# IRremote.net
KiCad netlist of a schematic drawn in EAGLE
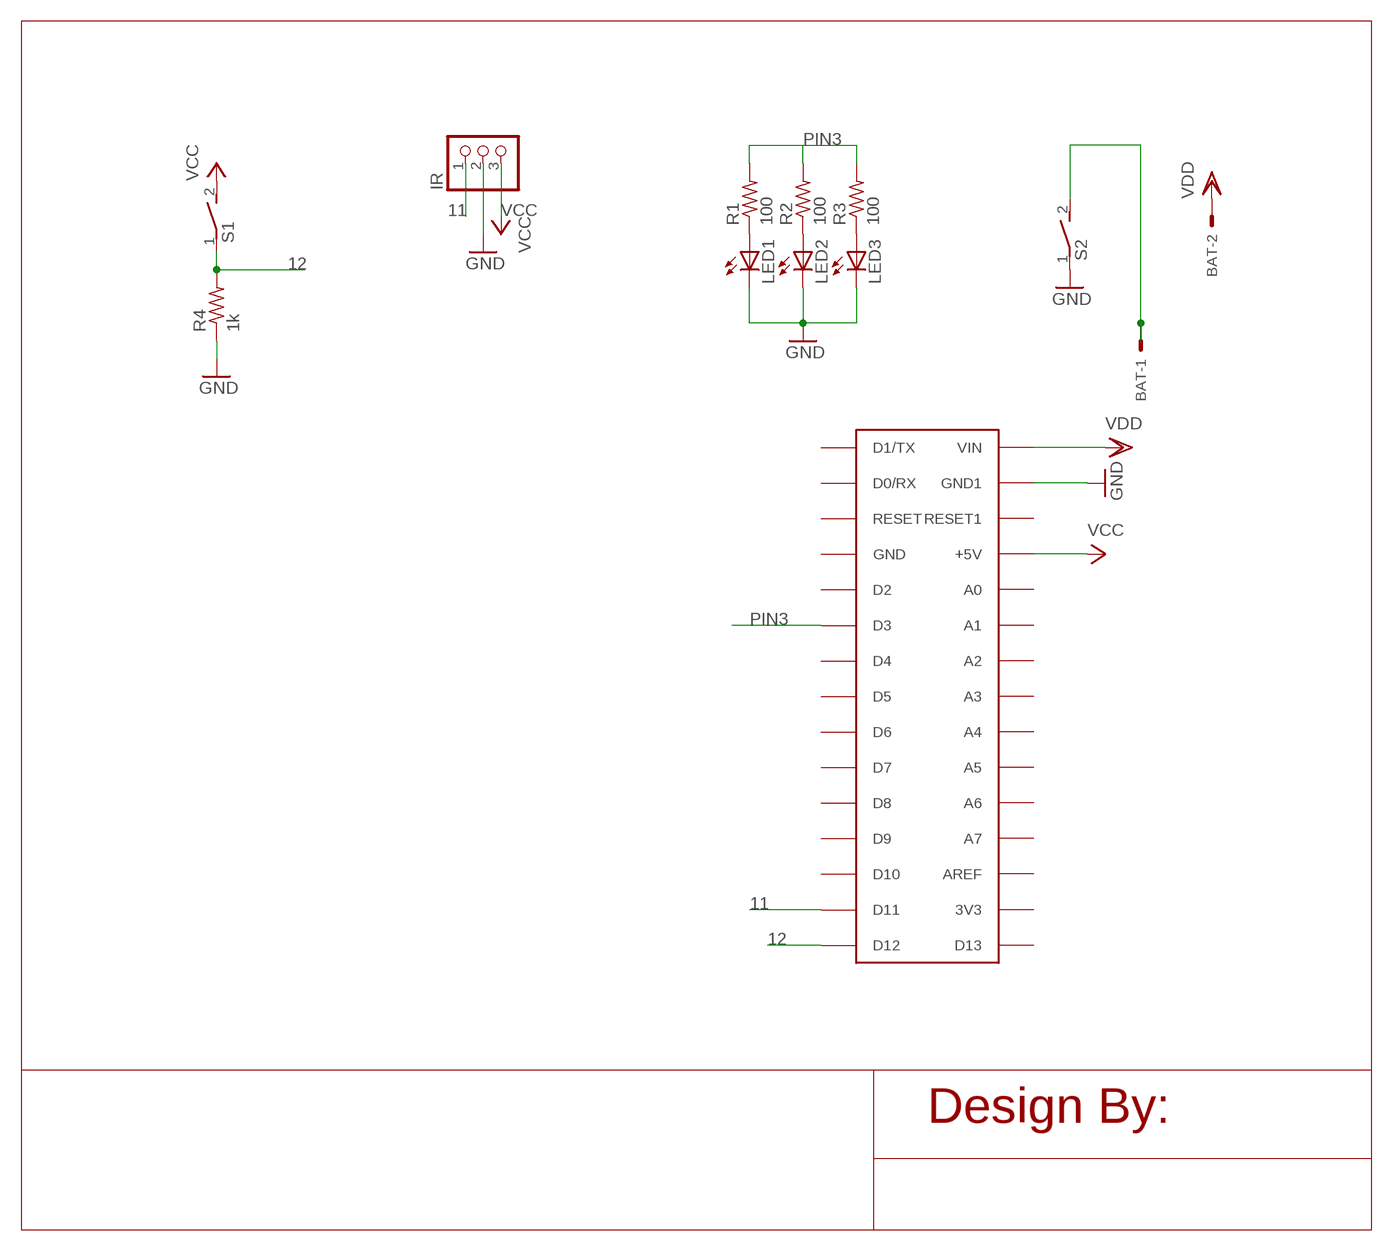
[diagram p0: schematic, sheet 1]

(export (version "E")
  (design (tool "Eeschema 10.0.6"))
  (components
    (comp (ref "ARDIUNO-NANO")
      (value "ARDUINONANO")
      (footprint "eagle-import:PDIP-32")
      (libsource (lib "eagle-import") (part "ARDUINONANO"))
    )
    (comp (ref "BAT")
      (value "22-23-2021")
      (footprint "eagle-import:22-23-2021")
      (fields (field (name "MF") "MOLEX"))
      (libsource (lib "eagle-import") (part "22-23-2021"))
    )
    (comp (ref "IR")
      (value "PINHD-1X3")
      (footprint "eagle-import:1X03")
      (libsource (lib "eagle-import") (part "PINHD-1X3"))
    )
    (comp (ref "LED1")
      (value "LED5MM")
      (footprint "eagle-import:LED5MM")
      (libsource (lib "eagle-import") (part "LED5MM"))
    )
    (comp (ref "LED2")
      (value "LED5MM")
      (footprint "eagle-import:LED5MM")
      (libsource (lib "eagle-import") (part "LED5MM"))
    )
    (comp (ref "LED3")
      (value "LED5MM")
      (footprint "eagle-import:LED5MM")
      (libsource (lib "eagle-import") (part "LED5MM"))
    )
    (comp (ref "R1")
      (value "100")
      (footprint "eagle-import:R0603")
      (libsource (lib "eagle-import") (part "R-US_R0603"))
    )
    (comp (ref "R2")
      (value "100")
      (footprint "eagle-import:R0603")
      (libsource (lib "eagle-import") (part "R-US_R0603"))
    )
    (comp (ref "R3")
      (value "100")
      (footprint "eagle-import:R0603")
      (libsource (lib "eagle-import") (part "R-US_R0603"))
    )
    (comp (ref "R4")
      (value "1k")
      (footprint "eagle-import:R0603")
      (libsource (lib "eagle-import") (part "R-US_R0603"))
    )
    (comp (ref "S1")
      (value "DS01E")
      (footprint "eagle-import:DS-01")
      (libsource (lib "eagle-import") (part "DS01E"))
    )
    (comp (ref "S2")
      (value "DS01E")
      (footprint "eagle-import:DS-01")
      (libsource (lib "eagle-import") (part "DS01E"))
    )
  )
  (nets
    (net (code "1") (name "/11") (class "Default")
      (node (ref "ARDIUNO-NANO") (pin "D11") (pinfunction "D11_D11") (pintype "bidirectional"))
      (node (ref "IR") (pin "1") (pinfunction "1_1") (pintype "passive"))
    )
    (net (code "2") (name "/12") (class "Default")
      (node (ref "ARDIUNO-NANO") (pin "D12") (pinfunction "D12_D12") (pintype "bidirectional"))
      (node (ref "R4") (pin "2") (pinfunction "2_2") (pintype "passive"))
      (node (ref "S1") (pin "1") (pinfunction "1_1") (pintype "passive"))
    )
    (net (code "3") (name "/PIN3") (class "Default")
      (node (ref "ARDIUNO-NANO") (pin "D3") (pinfunction "D3_D3") (pintype "bidirectional"))
      (node (ref "R1") (pin "2") (pinfunction "2_2") (pintype "passive"))
      (node (ref "R2") (pin "2") (pinfunction "2_2") (pintype "passive"))
      (node (ref "R3") (pin "2") (pinfunction "2_2") (pintype "passive"))
    )
    (net (code "4") (name "GND") (class "Default")
      (node (ref "ARDIUNO-NANO") (pin "GND1") (pinfunction "GND1_GND1") (pintype "bidirectional"))
      (node (ref "IR") (pin "2") (pinfunction "2_2") (pintype "passive"))
      (node (ref "LED1") (pin "K") (pinfunction "C_K") (pintype "passive"))
      (node (ref "LED2") (pin "K") (pinfunction "C_K") (pintype "passive"))
      (node (ref "LED3") (pin "K") (pinfunction "C_K") (pintype "passive"))
      (node (ref "R4") (pin "1") (pinfunction "1_1") (pintype "passive"))
      (node (ref "S2") (pin "1") (pinfunction "1_1") (pintype "passive"))
    )
    (net (code "5") (name "Net-(BATA-S)") (class "Default")
      (node (ref "BAT") (pin "1") (pinfunction "S_1") (pintype "passive"))
      (node (ref "S2") (pin "2") (pinfunction "2_2") (pintype "passive"))
    )
    (net (code "6") (name "Net-(LED1-PadA)") (class "Default")
      (node (ref "LED1") (pin "A") (pinfunction "A_A") (pintype "passive"))
      (node (ref "R1") (pin "1") (pinfunction "1_1") (pintype "passive"))
    )
    (net (code "7") (name "Net-(LED2-PadA)") (class "Default")
      (node (ref "LED2") (pin "A") (pinfunction "A_A") (pintype "passive"))
      (node (ref "R2") (pin "1") (pinfunction "1_1") (pintype "passive"))
    )
    (net (code "8") (name "Net-(LED3-PadA)") (class "Default")
      (node (ref "LED3") (pin "A") (pinfunction "A_A") (pintype "passive"))
      (node (ref "R3") (pin "1") (pinfunction "1_1") (pintype "passive"))
    )
    (net (code "9") (name "VCC") (class "Default")
      (node (ref "ARDIUNO-NANO") (pin "+5V") (pinfunction "+5V_+5V") (pintype "bidirectional"))
      (node (ref "IR") (pin "3") (pinfunction "3_3") (pintype "passive"))
      (node (ref "S1") (pin "2") (pinfunction "2_2") (pintype "passive"))
    )
    (net (code "10") (name "VDD") (class "Default")
      (node (ref "ARDIUNO-NANO") (pin "VIN") (pinfunction "VIN_VIN") (pintype "bidirectional"))
      (node (ref "BAT") (pin "2") (pinfunction "S_2") (pintype "passive"))
    )
    (net (code "11") (name "unconnected-(ARDIUNO-NANO-Pad3V3)") (class "Default")
      (node (ref "ARDIUNO-NANO") (pin "3V3") (pinfunction "3V3_3V3") (pintype "bidirectional"))
    )
    (net (code "12") (name "unconnected-(ARDIUNO-NANO-PadA0)") (class "Default")
      (node (ref "ARDIUNO-NANO") (pin "A0") (pinfunction "A0_A0") (pintype "bidirectional"))
    )
    (net (code "13") (name "unconnected-(ARDIUNO-NANO-PadA1)") (class "Default")
      (node (ref "ARDIUNO-NANO") (pin "A1") (pinfunction "A1_A1") (pintype "bidirectional"))
    )
    (net (code "14") (name "unconnected-(ARDIUNO-NANO-PadA2)") (class "Default")
      (node (ref "ARDIUNO-NANO") (pin "A2") (pinfunction "A2_A2") (pintype "bidirectional"))
    )
    (net (code "15") (name "unconnected-(ARDIUNO-NANO-PadA3)") (class "Default")
      (node (ref "ARDIUNO-NANO") (pin "A3") (pinfunction "A3_A3") (pintype "bidirectional"))
    )
    (net (code "16") (name "unconnected-(ARDIUNO-NANO-PadA4)") (class "Default")
      (node (ref "ARDIUNO-NANO") (pin "A4") (pinfunction "A4_A4") (pintype "bidirectional"))
    )
    (net (code "17") (name "unconnected-(ARDIUNO-NANO-PadA5)") (class "Default")
      (node (ref "ARDIUNO-NANO") (pin "A5") (pinfunction "A5_A5") (pintype "bidirectional"))
    )
    (net (code "18") (name "unconnected-(ARDIUNO-NANO-PadA6)") (class "Default")
      (node (ref "ARDIUNO-NANO") (pin "A6") (pinfunction "A6_A6") (pintype "bidirectional"))
    )
    (net (code "19") (name "unconnected-(ARDIUNO-NANO-PadA7)") (class "Default")
      (node (ref "ARDIUNO-NANO") (pin "A7") (pinfunction "A7_A7") (pintype "bidirectional"))
    )
    (net (code "20") (name "unconnected-(ARDIUNO-NANO-PadAREF)") (class "Default")
      (node (ref "ARDIUNO-NANO") (pin "AREF") (pinfunction "AREF_AREF") (pintype "bidirectional"))
    )
    (net (code "21") (name "unconnected-(ARDIUNO-NANO-PadD0{slash}RX)") (class "Default")
      (node (ref "ARDIUNO-NANO") (pin "D0/RX") (pinfunction "D0/RX_D0/RX") (pintype "bidirectional"))
    )
    (net (code "22") (name "unconnected-(ARDIUNO-NANO-PadD1{slash}TX)") (class "Default")
      (node (ref "ARDIUNO-NANO") (pin "D1/TX") (pinfunction "D1/TX_D1/TX") (pintype "bidirectional"))
    )
    (net (code "23") (name "unconnected-(ARDIUNO-NANO-PadD2)") (class "Default")
      (node (ref "ARDIUNO-NANO") (pin "D2") (pinfunction "D2_D2") (pintype "bidirectional"))
    )
    (net (code "24") (name "unconnected-(ARDIUNO-NANO-PadD4)") (class "Default")
      (node (ref "ARDIUNO-NANO") (pin "D4") (pinfunction "D4_D4") (pintype "bidirectional"))
    )
    (net (code "25") (name "unconnected-(ARDIUNO-NANO-PadD5)") (class "Default")
      (node (ref "ARDIUNO-NANO") (pin "D5") (pinfunction "D5_D5") (pintype "bidirectional"))
    )
    (net (code "26") (name "unconnected-(ARDIUNO-NANO-PadD6)") (class "Default")
      (node (ref "ARDIUNO-NANO") (pin "D6") (pinfunction "D6_D6") (pintype "bidirectional"))
    )
    (net (code "27") (name "unconnected-(ARDIUNO-NANO-PadD7)") (class "Default")
      (node (ref "ARDIUNO-NANO") (pin "D7") (pinfunction "D7_D7") (pintype "bidirectional"))
    )
    (net (code "28") (name "unconnected-(ARDIUNO-NANO-PadD8)") (class "Default")
      (node (ref "ARDIUNO-NANO") (pin "D8") (pinfunction "D8_D8") (pintype "bidirectional"))
    )
    (net (code "29") (name "unconnected-(ARDIUNO-NANO-PadD9)") (class "Default")
      (node (ref "ARDIUNO-NANO") (pin "D9") (pinfunction "D9_D9") (pintype "bidirectional"))
    )
    (net (code "30") (name "unconnected-(ARDIUNO-NANO-PadD10)") (class "Default")
      (node (ref "ARDIUNO-NANO") (pin "D10") (pinfunction "D10_D10") (pintype "bidirectional"))
    )
    (net (code "31") (name "unconnected-(ARDIUNO-NANO-PadD13)") (class "Default")
      (node (ref "ARDIUNO-NANO") (pin "D13") (pinfunction "D13_D13") (pintype "bidirectional"))
    )
    (net (code "32") (name "unconnected-(ARDIUNO-NANO-PadGND)") (class "Default")
      (node (ref "ARDIUNO-NANO") (pin "GND") (pinfunction "GND_GND") (pintype "bidirectional"))
    )
    (net (code "33") (name "unconnected-(ARDIUNO-NANO-PadRESET)") (class "Default")
      (node (ref "ARDIUNO-NANO") (pin "RESET") (pinfunction "RESET_RESET") (pintype "bidirectional"))
    )
    (net (code "34") (name "unconnected-(ARDIUNO-NANO-PadRESET1)") (class "Default")
      (node (ref "ARDIUNO-NANO") (pin "RESET1") (pinfunction "RESET1_RESET1") (pintype "bidirectional"))
    )
  )
)
